# Adafruit_ADXL377.net
KiCad netlist of a schematic drawn in EAGLE
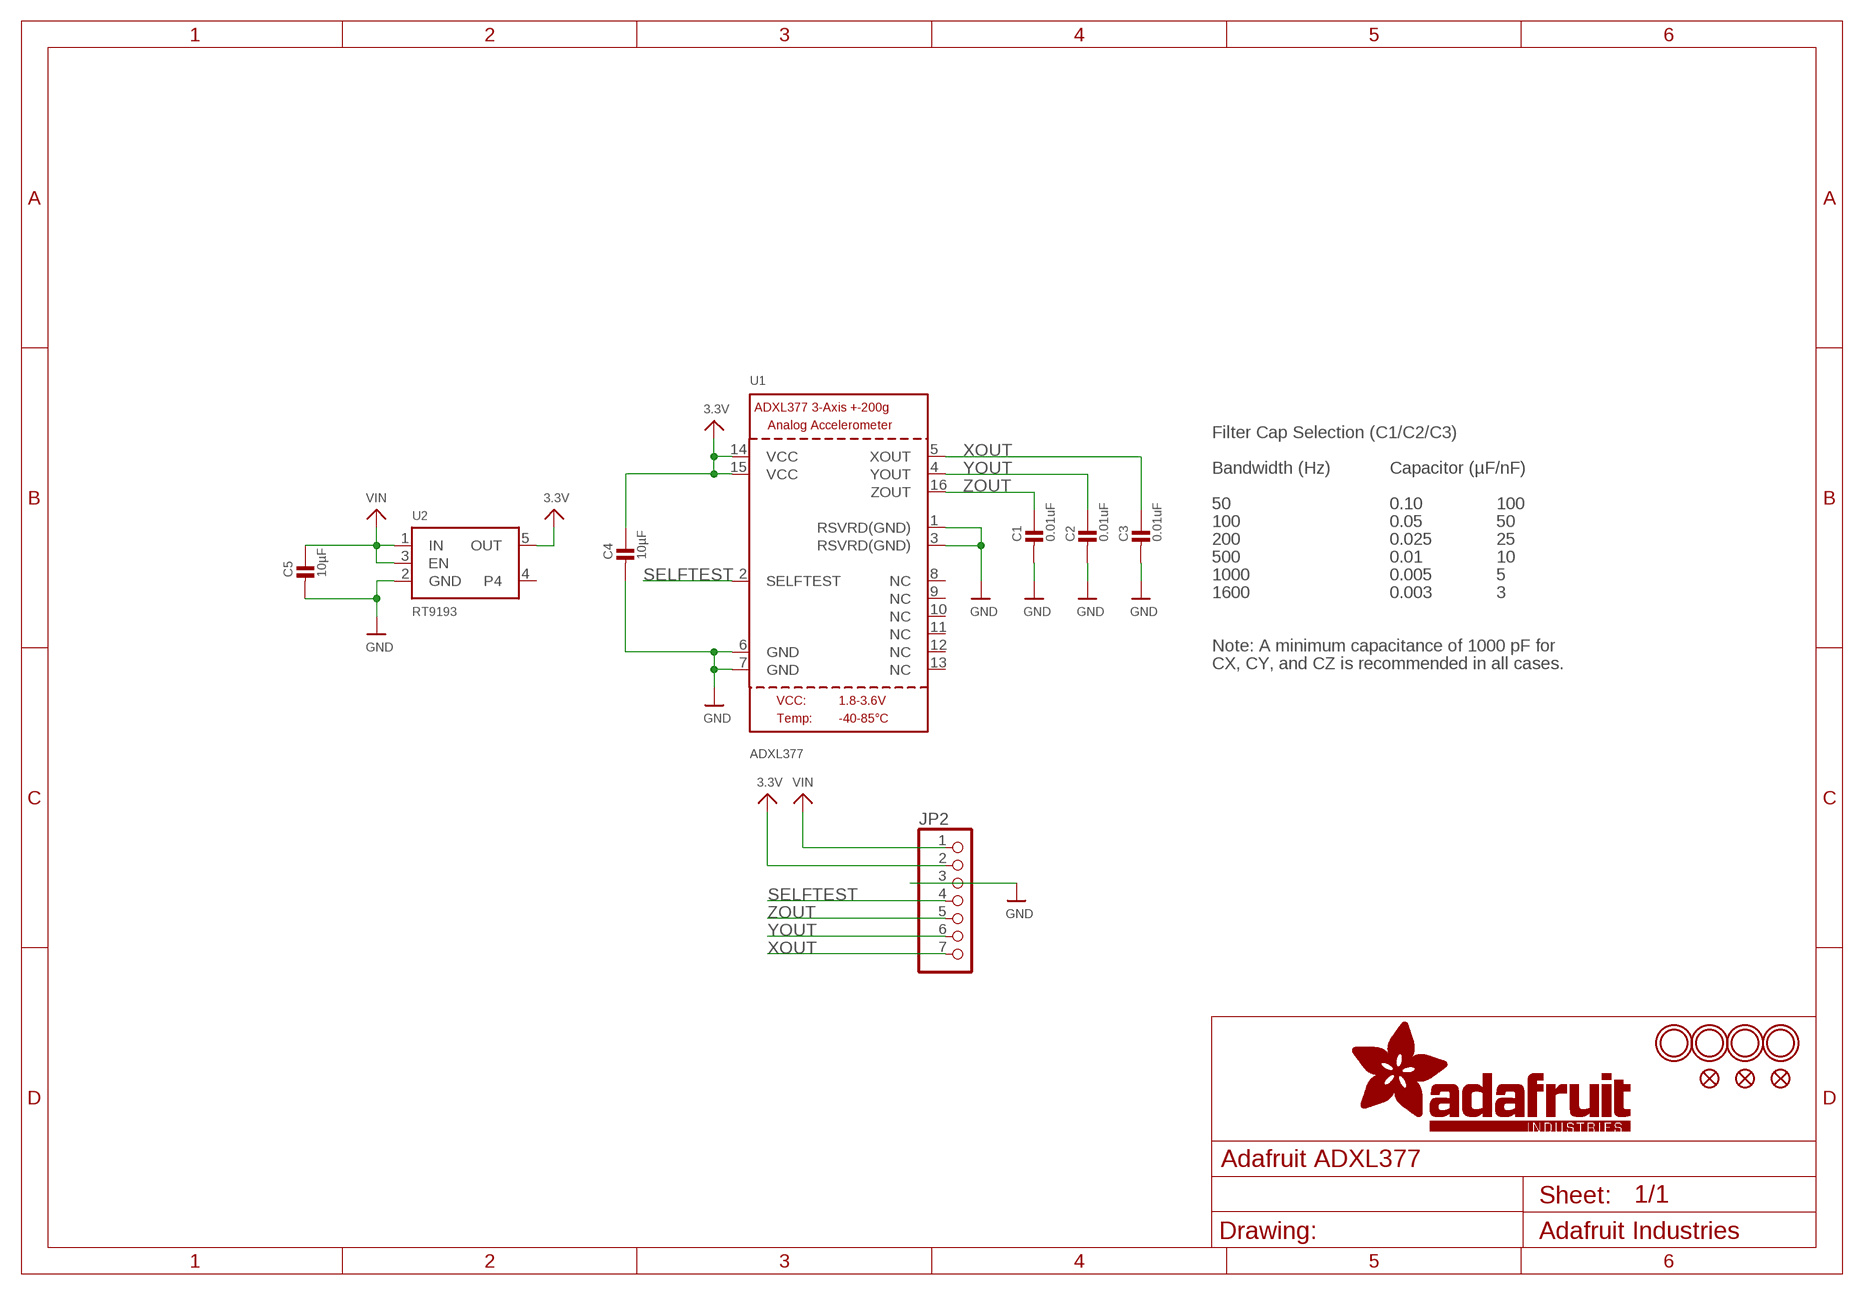
[diagram p0: schematic, sheet 1]

(export (version "E")
  (design (tool "Eeschema 10.0.6"))
  (components
    (comp (ref "C1")
      (value "0.01uF")
      (footprint "eagle-import:_0805")
      (libsource (lib "eagle-import") (part "CAP_CERAMIC_0805"))
    )
    (comp (ref "C2")
      (value "0.01uF")
      (footprint "eagle-import:_0805")
      (libsource (lib "eagle-import") (part "CAP_CERAMIC_0805"))
    )
    (comp (ref "C3")
      (value "0.01uF")
      (footprint "eagle-import:_0805")
      (libsource (lib "eagle-import") (part "CAP_CERAMIC_0805"))
    )
    (comp (ref "C4")
      (value "10µF")
      (footprint "eagle-import:_0805")
      (libsource (lib "eagle-import") (part "CAP_CERAMIC_0805"))
    )
    (comp (ref "C5")
      (value "10µF")
      (footprint "eagle-import:_0805")
      (libsource (lib "eagle-import") (part "CAP_CERAMIC_0805"))
    )
    (comp (ref "FID1")
      (value "FIDUCIAL\"\"")
      (footprint "eagle-import:FIDUCIAL_1MM")
      (libsource (lib "eagle-import") (part "FIDUCIAL{dblquote}{dblquote}"))
    )
    (comp (ref "FID2")
      (value "FIDUCIAL\"\"")
      (footprint "eagle-import:FIDUCIAL_1MM")
      (libsource (lib "eagle-import") (part "FIDUCIAL{dblquote}{dblquote}"))
    )
    (comp (ref "FID3")
      (value "FIDUCIAL\"\"")
      (footprint "eagle-import:FIDUCIAL_1MM")
      (libsource (lib "eagle-import") (part "FIDUCIAL{dblquote}{dblquote}"))
    )
    (comp (ref "JP2")
      (value "HEADER-1X770MIL")
      (footprint "eagle-import:1X07_ROUND_70")
      (libsource (lib "eagle-import") (part "HEADER-1X770MIL"))
    )
    (comp (ref "U$2")
      (value "MOUNTINGHOLE2.5")
      (footprint "eagle-import:MOUNTINGHOLE_2.5_PLATED")
      (libsource (lib "eagle-import") (part "MOUNTINGHOLE2.5"))
    )
    (comp (ref "U$3")
      (value "MOUNTINGHOLE2.5")
      (footprint "eagle-import:MOUNTINGHOLE_2.5_PLATED")
      (libsource (lib "eagle-import") (part "MOUNTINGHOLE2.5"))
    )
    (comp (ref "U$17")
      (value "MOUNTINGHOLE2.5")
      (footprint "eagle-import:MOUNTINGHOLE_2.5_PLATED")
      (libsource (lib "eagle-import") (part "MOUNTINGHOLE2.5"))
    )
    (comp (ref "U$18")
      (value "MOUNTINGHOLE2.5")
      (footprint "eagle-import:MOUNTINGHOLE_2.5_PLATED")
      (libsource (lib "eagle-import") (part "MOUNTINGHOLE2.5"))
    )
    (comp (ref "U1")
      (value "ADXL377")
      (footprint "eagle-import:LFCSP16_LQ")
      (libsource (lib "eagle-import") (part "ACCEL_ADXL377"))
    )
    (comp (ref "U2")
      (value "RT9193")
      (footprint "eagle-import:SOT23-5")
      (libsource (lib "eagle-import") (part "VREG_SOT23-5"))
    )
  )
  (nets
    (net (code "1") (name "/SELFTEST") (class "Default")
      (node (ref "JP2") (pin "4") (pinfunction "4_4") (pintype "passive"))
      (node (ref "U1") (pin "2") (pinfunction "SELFTEST_2") (pintype "bidirectional"))
    )
    (net (code "2") (name "/XOUT") (class "Default")
      (node (ref "C3") (pin "1") (pinfunction "P$1_1") (pintype "passive"))
      (node (ref "JP2") (pin "7") (pinfunction "7_7") (pintype "passive"))
      (node (ref "U1") (pin "5") (pinfunction "XOUT_5") (pintype "output"))
    )
    (net (code "3") (name "/YOUT") (class "Default")
      (node (ref "C2") (pin "1") (pinfunction "P$1_1") (pintype "passive"))
      (node (ref "JP2") (pin "6") (pinfunction "6_6") (pintype "passive"))
      (node (ref "U1") (pin "4") (pinfunction "YOUT_4") (pintype "output"))
    )
    (net (code "4") (name "/ZOUT") (class "Default")
      (node (ref "C1") (pin "1") (pinfunction "P$1_1") (pintype "passive"))
      (node (ref "JP2") (pin "5") (pinfunction "5_5") (pintype "passive"))
      (node (ref "U1") (pin "16") (pinfunction "ZOUT_16") (pintype "output"))
    )
    (net (code "5") (name "3.3V") (class "Default")
      (node (ref "C4") (pin "1") (pinfunction "P$1_1") (pintype "passive"))
      (node (ref "JP2") (pin "2") (pinfunction "2_2") (pintype "passive"))
      (node (ref "U1") (pin "14") (pinfunction "VCC_14") (pintype "power_in"))
      (node (ref "U1") (pin "15") (pinfunction "VCC_15") (pintype "power_in"))
      (node (ref "U2") (pin "5") (pinfunction "OUT_5") (pintype "power_in"))
    )
    (net (code "6") (name "GND") (class "Default")
      (node (ref "C1") (pin "2") (pinfunction "P$2_2") (pintype "passive"))
      (node (ref "C2") (pin "2") (pinfunction "P$2_2") (pintype "passive"))
      (node (ref "C3") (pin "2") (pinfunction "P$2_2") (pintype "passive"))
      (node (ref "C4") (pin "2") (pinfunction "P$2_2") (pintype "passive"))
      (node (ref "C5") (pin "2") (pinfunction "P$2_2") (pintype "passive"))
      (node (ref "JP2") (pin "3") (pinfunction "3_3") (pintype "passive"))
      (node (ref "U1") (pin "1") (pinfunction "RSVRD(GND)_1") (pintype "bidirectional"))
      (node (ref "U1") (pin "3") (pinfunction "RSVRD(GND)_3") (pintype "bidirectional"))
      (node (ref "U1") (pin "6") (pinfunction "GND_6") (pintype "power_in"))
      (node (ref "U1") (pin "7") (pinfunction "GND_7") (pintype "power_in"))
      (node (ref "U2") (pin "2") (pinfunction "GND_2") (pintype "power_in"))
    )
    (net (code "7") (name "VIN") (class "Default")
      (node (ref "C5") (pin "1") (pinfunction "P$1_1") (pintype "passive"))
      (node (ref "JP2") (pin "1") (pinfunction "1_1") (pintype "passive"))
      (node (ref "U2") (pin "1") (pinfunction "IN_1") (pintype "power_in"))
      (node (ref "U2") (pin "3") (pinfunction "EN_3") (pintype "input"))
    )
    (net (code "8") (name "unconnected-(U1-NC-Pad8)") (class "Default")
      (node (ref "U1") (pin "8") (pinfunction "NC_8") (pintype "no_connect"))
    )
    (net (code "9") (name "unconnected-(U1-NC-Pad9)") (class "Default")
      (node (ref "U1") (pin "9") (pinfunction "NC_9") (pintype "no_connect"))
    )
    (net (code "10") (name "unconnected-(U1-NC-Pad10)") (class "Default")
      (node (ref "U1") (pin "10") (pinfunction "NC_10") (pintype "no_connect"))
    )
    (net (code "11") (name "unconnected-(U1-NC-Pad11)") (class "Default")
      (node (ref "U1") (pin "11") (pinfunction "NC_11") (pintype "no_connect"))
    )
    (net (code "12") (name "unconnected-(U1-NC-Pad12)") (class "Default")
      (node (ref "U1") (pin "12") (pinfunction "NC_12") (pintype "no_connect"))
    )
    (net (code "13") (name "unconnected-(U1-NC-Pad13)") (class "Default")
      (node (ref "U1") (pin "13") (pinfunction "NC_13") (pintype "no_connect"))
    )
    (net (code "14") (name "unconnected-(U2-P4-Pad4)") (class "Default")
      (node (ref "U2") (pin "4") (pinfunction "P4_4") (pintype "bidirectional"))
    )
  )
)
